# C64_Keyb-Test.net
KiCad netlist of a schematic drawn in EAGLE
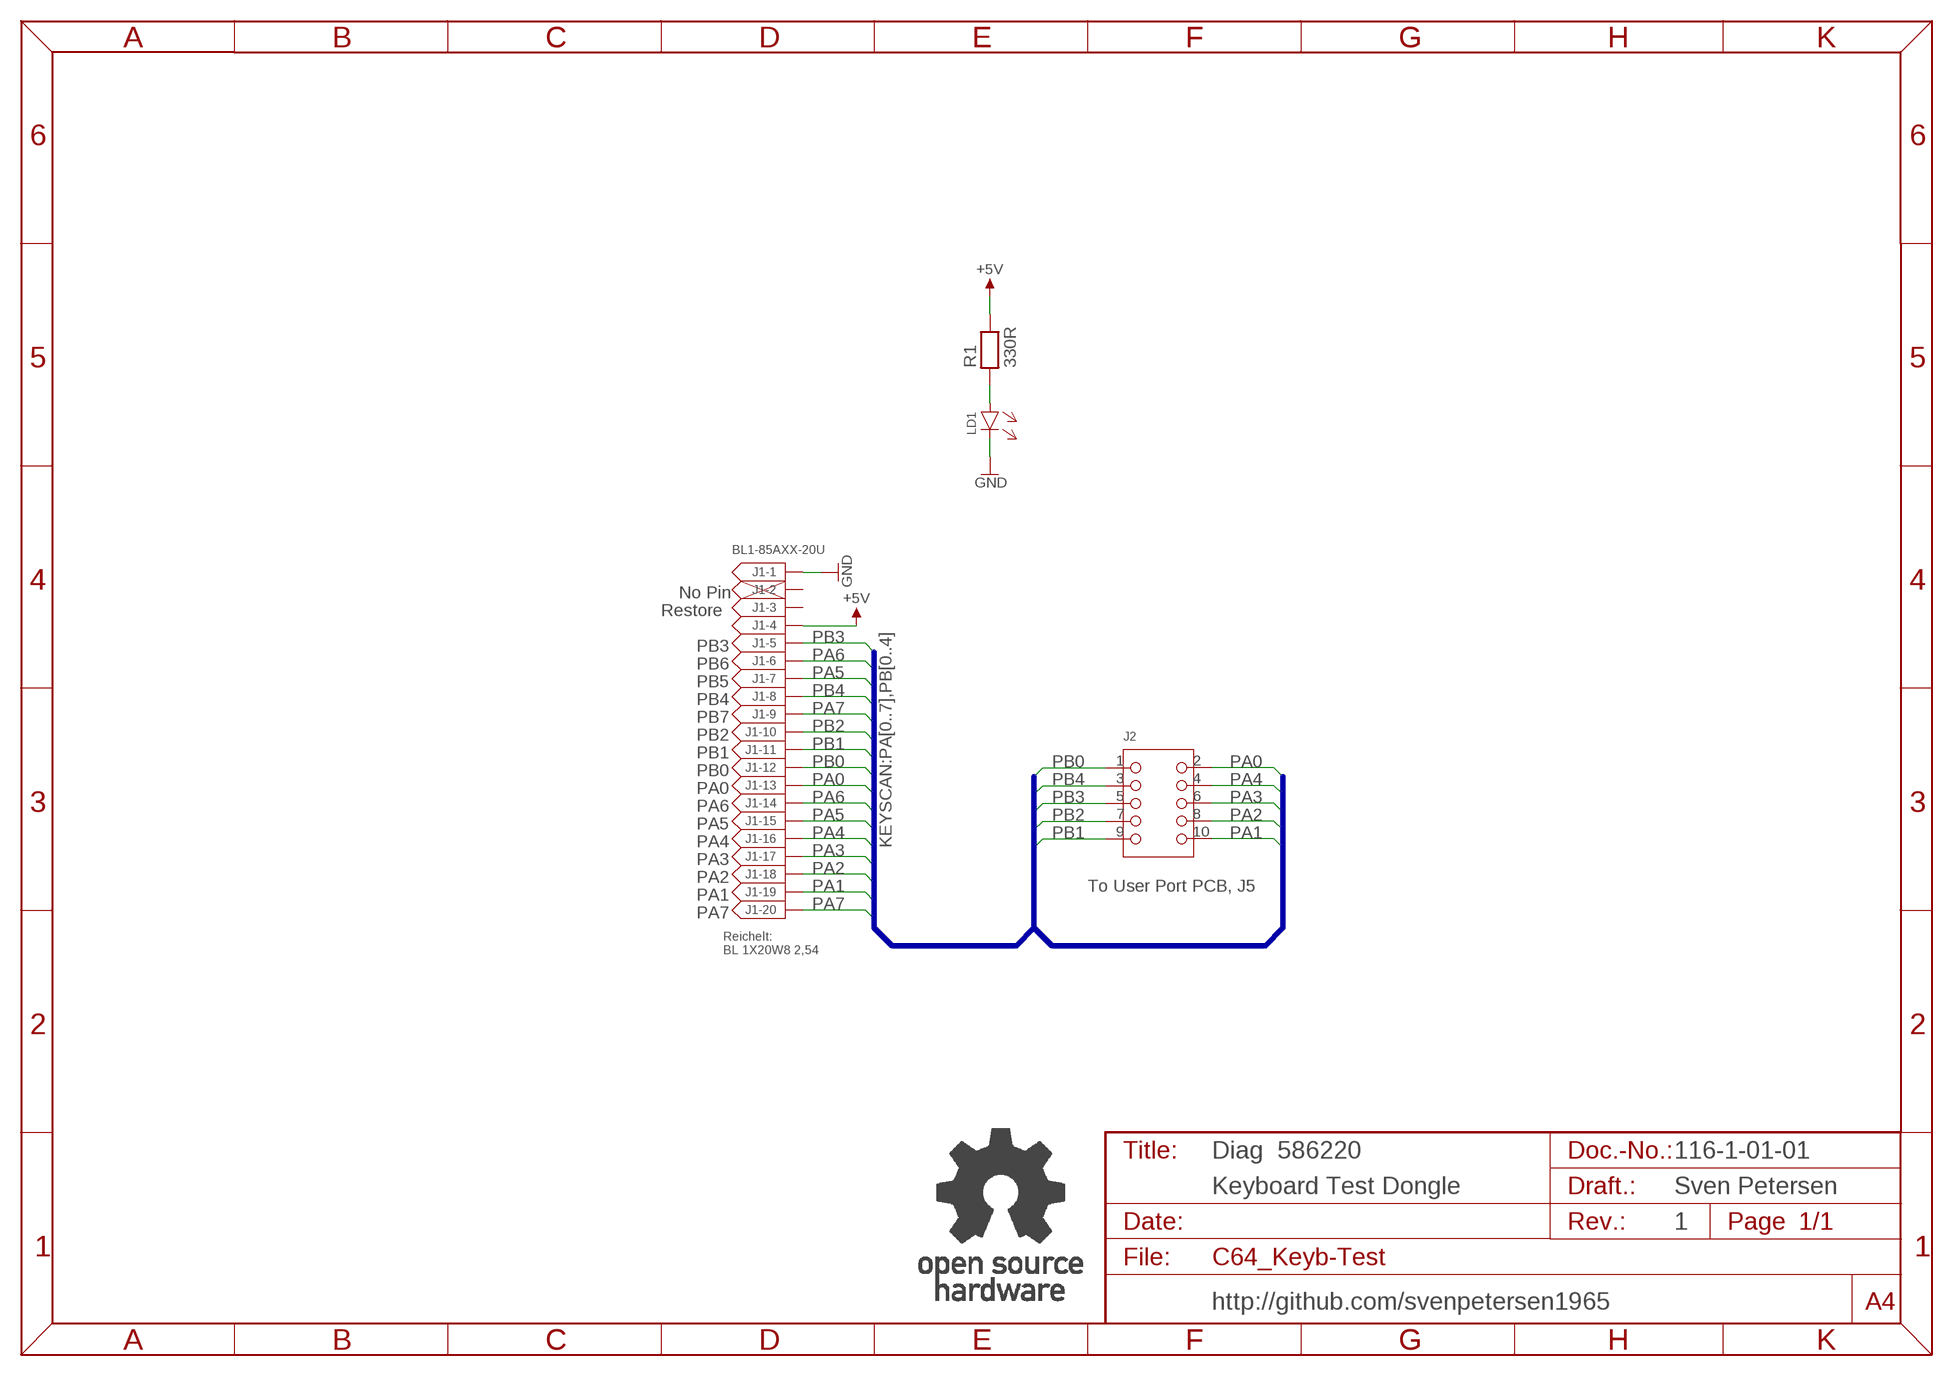
[diagram p0: schematic, sheet 1]

(export (version "E")
  (design (tool "Eeschema 10.0.6"))
  (components
    (comp (ref "J1")
      (value "BL1-85AXX-20U")
      (footprint "eagle-import:BL1-85AXX-20U")
      (libsource (lib "eagle-import") (part "BL1-85AXX-20U"))
    )
    (comp (ref "J2")
      (value "2X05WV")
      (footprint "eagle-import:2X05WV")
      (libsource (lib "eagle-import") (part "2X05WV"))
    )
    (comp (ref "LD1")
      (value "3MM")
      (footprint "eagle-import:3MM")
      (libsource (lib "eagle-import") (part "3MM"))
    )
    (comp (ref "R1")
      (value "330R")
      (footprint "eagle-import:R-10")
      (libsource (lib "eagle-import") (part "RES04"))
    )
    (comp (ref "U$9")
      (value "OPEN_SOURCE_HW")
      (footprint "eagle-import:OPENHW")
      (libsource (lib "eagle-import") (part "OPEN_SOURCE_HW"))
    )
  )
  (nets
    (net (code "1") (name "+5V") (class "Default")
      (node (ref "J1") (pin "4") (pinfunction "1_4") (pintype "bidirectional"))
      (node (ref "R1") (pin "2") (pinfunction "2_2") (pintype "passive"))
    )
    (net (code "2") (name "/PA0") (class "Default")
      (node (ref "J1") (pin "13") (pinfunction "1_13") (pintype "bidirectional"))
      (node (ref "J2") (pin "2") (pinfunction "2_2") (pintype "passive"))
    )
    (net (code "3") (name "/PA1") (class "Default")
      (node (ref "J1") (pin "19") (pinfunction "1_19") (pintype "bidirectional"))
      (node (ref "J2") (pin "10") (pinfunction "10_10") (pintype "passive"))
    )
    (net (code "4") (name "/PA2") (class "Default")
      (node (ref "J1") (pin "18") (pinfunction "1_18") (pintype "bidirectional"))
      (node (ref "J2") (pin "8") (pinfunction "8_8") (pintype "passive"))
    )
    (net (code "5") (name "/PA3") (class "Default")
      (node (ref "J1") (pin "17") (pinfunction "1_17") (pintype "bidirectional"))
      (node (ref "J2") (pin "6") (pinfunction "6_6") (pintype "passive"))
    )
    (net (code "6") (name "/PA4") (class "Default")
      (node (ref "J1") (pin "16") (pinfunction "1_16") (pintype "bidirectional"))
      (node (ref "J2") (pin "4") (pinfunction "4_4") (pintype "passive"))
    )
    (net (code "7") (name "/PA5") (class "Default")
      (node (ref "J1") (pin "15") (pinfunction "1_15") (pintype "bidirectional"))
      (node (ref "J1") (pin "7") (pinfunction "1_7") (pintype "bidirectional"))
    )
    (net (code "8") (name "/PA6") (class "Default")
      (node (ref "J1") (pin "14") (pinfunction "1_14") (pintype "bidirectional"))
      (node (ref "J1") (pin "6") (pinfunction "1_6") (pintype "bidirectional"))
    )
    (net (code "9") (name "/PA7") (class "Default")
      (node (ref "J1") (pin "20") (pinfunction "1_20") (pintype "bidirectional"))
      (node (ref "J1") (pin "9") (pinfunction "1_9") (pintype "bidirectional"))
    )
    (net (code "10") (name "/PB0") (class "Default")
      (node (ref "J1") (pin "12") (pinfunction "1_12") (pintype "bidirectional"))
      (node (ref "J2") (pin "1") (pinfunction "1_1") (pintype "passive"))
    )
    (net (code "11") (name "/PB1") (class "Default")
      (node (ref "J1") (pin "11") (pinfunction "1_11") (pintype "bidirectional"))
      (node (ref "J2") (pin "9") (pinfunction "9_9") (pintype "passive"))
    )
    (net (code "12") (name "/PB2") (class "Default")
      (node (ref "J1") (pin "10") (pinfunction "1_10") (pintype "bidirectional"))
      (node (ref "J2") (pin "7") (pinfunction "7_7") (pintype "passive"))
    )
    (net (code "13") (name "/PB3") (class "Default")
      (node (ref "J1") (pin "5") (pinfunction "1_5") (pintype "bidirectional"))
      (node (ref "J2") (pin "5") (pinfunction "5_5") (pintype "passive"))
    )
    (net (code "14") (name "/PB4") (class "Default")
      (node (ref "J1") (pin "8") (pinfunction "1_8") (pintype "bidirectional"))
      (node (ref "J2") (pin "3") (pinfunction "3_3") (pintype "passive"))
    )
    (net (code "16") (name "GND") (class "Default")
      (node (ref "J1") (pin "1") (pinfunction "1_1") (pintype "bidirectional"))
      (node (ref "LD1") (pin "C") (pinfunction "K_C") (pintype "bidirectional"))
    )
    (net (code "17") (name "Net-(LD1-PadA)") (class "Default")
      (node (ref "LD1") (pin "A") (pinfunction "A_A") (pintype "bidirectional"))
      (node (ref "R1") (pin "1") (pinfunction "1_1") (pintype "passive"))
    )
    (net (code "18") (name "unconnected-(J1L-1-Pad2)") (class "Default")
      (node (ref "J1") (pin "2") (pinfunction "1_2") (pintype "bidirectional"))
    )
    (net (code "19") (name "unconnected-(J1N-1-Pad3)") (class "Default")
      (node (ref "J1") (pin "3") (pinfunction "1_3") (pintype "bidirectional"))
    )
  )
)
